# PowerDistribution.net
KiCad netlist of a schematic drawn in Altium Designer
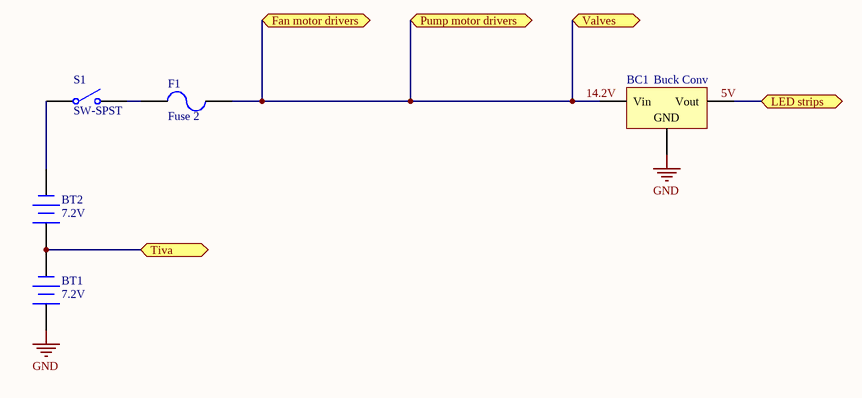
[diagram p0: PowerDistribution.SchDoc]

(export (version "E")
  (design (tool "Eeschema 10.0.6"))
  (components
    (comp (ref "BC1")
      (value "Buck Conv")
      (footprint "D2PAK_L")
      (description "Voltage Regulator")
      (fields (field (name "PUBLISHER") "Altium Limited"))
      (libsource (lib "Miscellaneous Devices") (part "Volt Reg"))
    )
    (comp (ref "BT1")
      (value "7.2V")
      (footprint "BAT-2")
      (description "Multicell Battery")
      (fields (field (name "MANUFACTURER") "Generic Components"))
      (libsource (lib "ME218_BaseLib") (part "Battery"))
    )
    (comp (ref "BT2")
      (value "7.2V")
      (footprint "BAT-2")
      (description "Multicell Battery")
      (fields (field (name "MANUFACTURER") "Generic Components"))
      (libsource (lib "ME218_BaseLib") (part "Battery"))
    )
    (comp (ref "F1")
      (value "Fuse 2")
      (footprint "PIN-W2/E2.8")
      (description "Fuse")
      (fields
        (field (name "MANUFACTURER") "Generic Components")
        (field (name "PUBLISHER") "Altium Hobart Technology Centre")
      )
      (libsource (lib "ME218_BaseLib") (part "Fuse 2"))
    )
    (comp (ref "S1")
      (value "SW-SPST")
      (footprint "SPST-2")
      (description "Single-Pole, Single-Throw Switch")
      (fields (field (name "MANUFACTURER") "Generic Components"))
      (libsource (lib "ME218_BaseLib") (part "SW-SPST"))
    )
  )
  (nets
    (net (code "2") (name "/14.2V") (class "Default")
      (node (ref "BC1") (pin "1") (pinfunction "Vin_1") (pintype "passive"))
      (node (ref "F1") (pin "1") (pinfunction "1_1") (pintype "passive"))
    )
    (net (code "3") (name "/LED strips") (class "Default")
      (node (ref "BC1") (pin "3") (pinfunction "Vout_3") (pintype "passive"))
    )
    (net (code "4") (name "/Tiva") (class "Default")
      (node (ref "BT1") (pin "2") (pinfunction "-_2") (pintype "passive"))
      (node (ref "BT2") (pin "1") (pinfunction "+_1") (pintype "passive"))
    )
    (net (code "5") (name "GND") (class "Default")
      (node (ref "BC1") (pin "2") (pinfunction "GND_2") (pintype "passive"))
      (node (ref "BT1") (pin "1") (pinfunction "+_1") (pintype "passive"))
    )
    (net (code "6") (name "Net-(BT2--)") (class "Default")
      (node (ref "BT2") (pin "2") (pinfunction "-_2") (pintype "passive"))
      (node (ref "S1") (pin "1") (pinfunction "COMMON_1") (pintype "passive"))
    )
    (net (code "7") (name "Net-(S1-NO)") (class "Default")
      (node (ref "F1") (pin "2") (pinfunction "2_2") (pintype "passive"))
      (node (ref "S1") (pin "2") (pinfunction "NO_2") (pintype "passive"))
    )
  )
)
